# StepperDriver.net
KiCad netlist of a schematic drawn in EAGLE
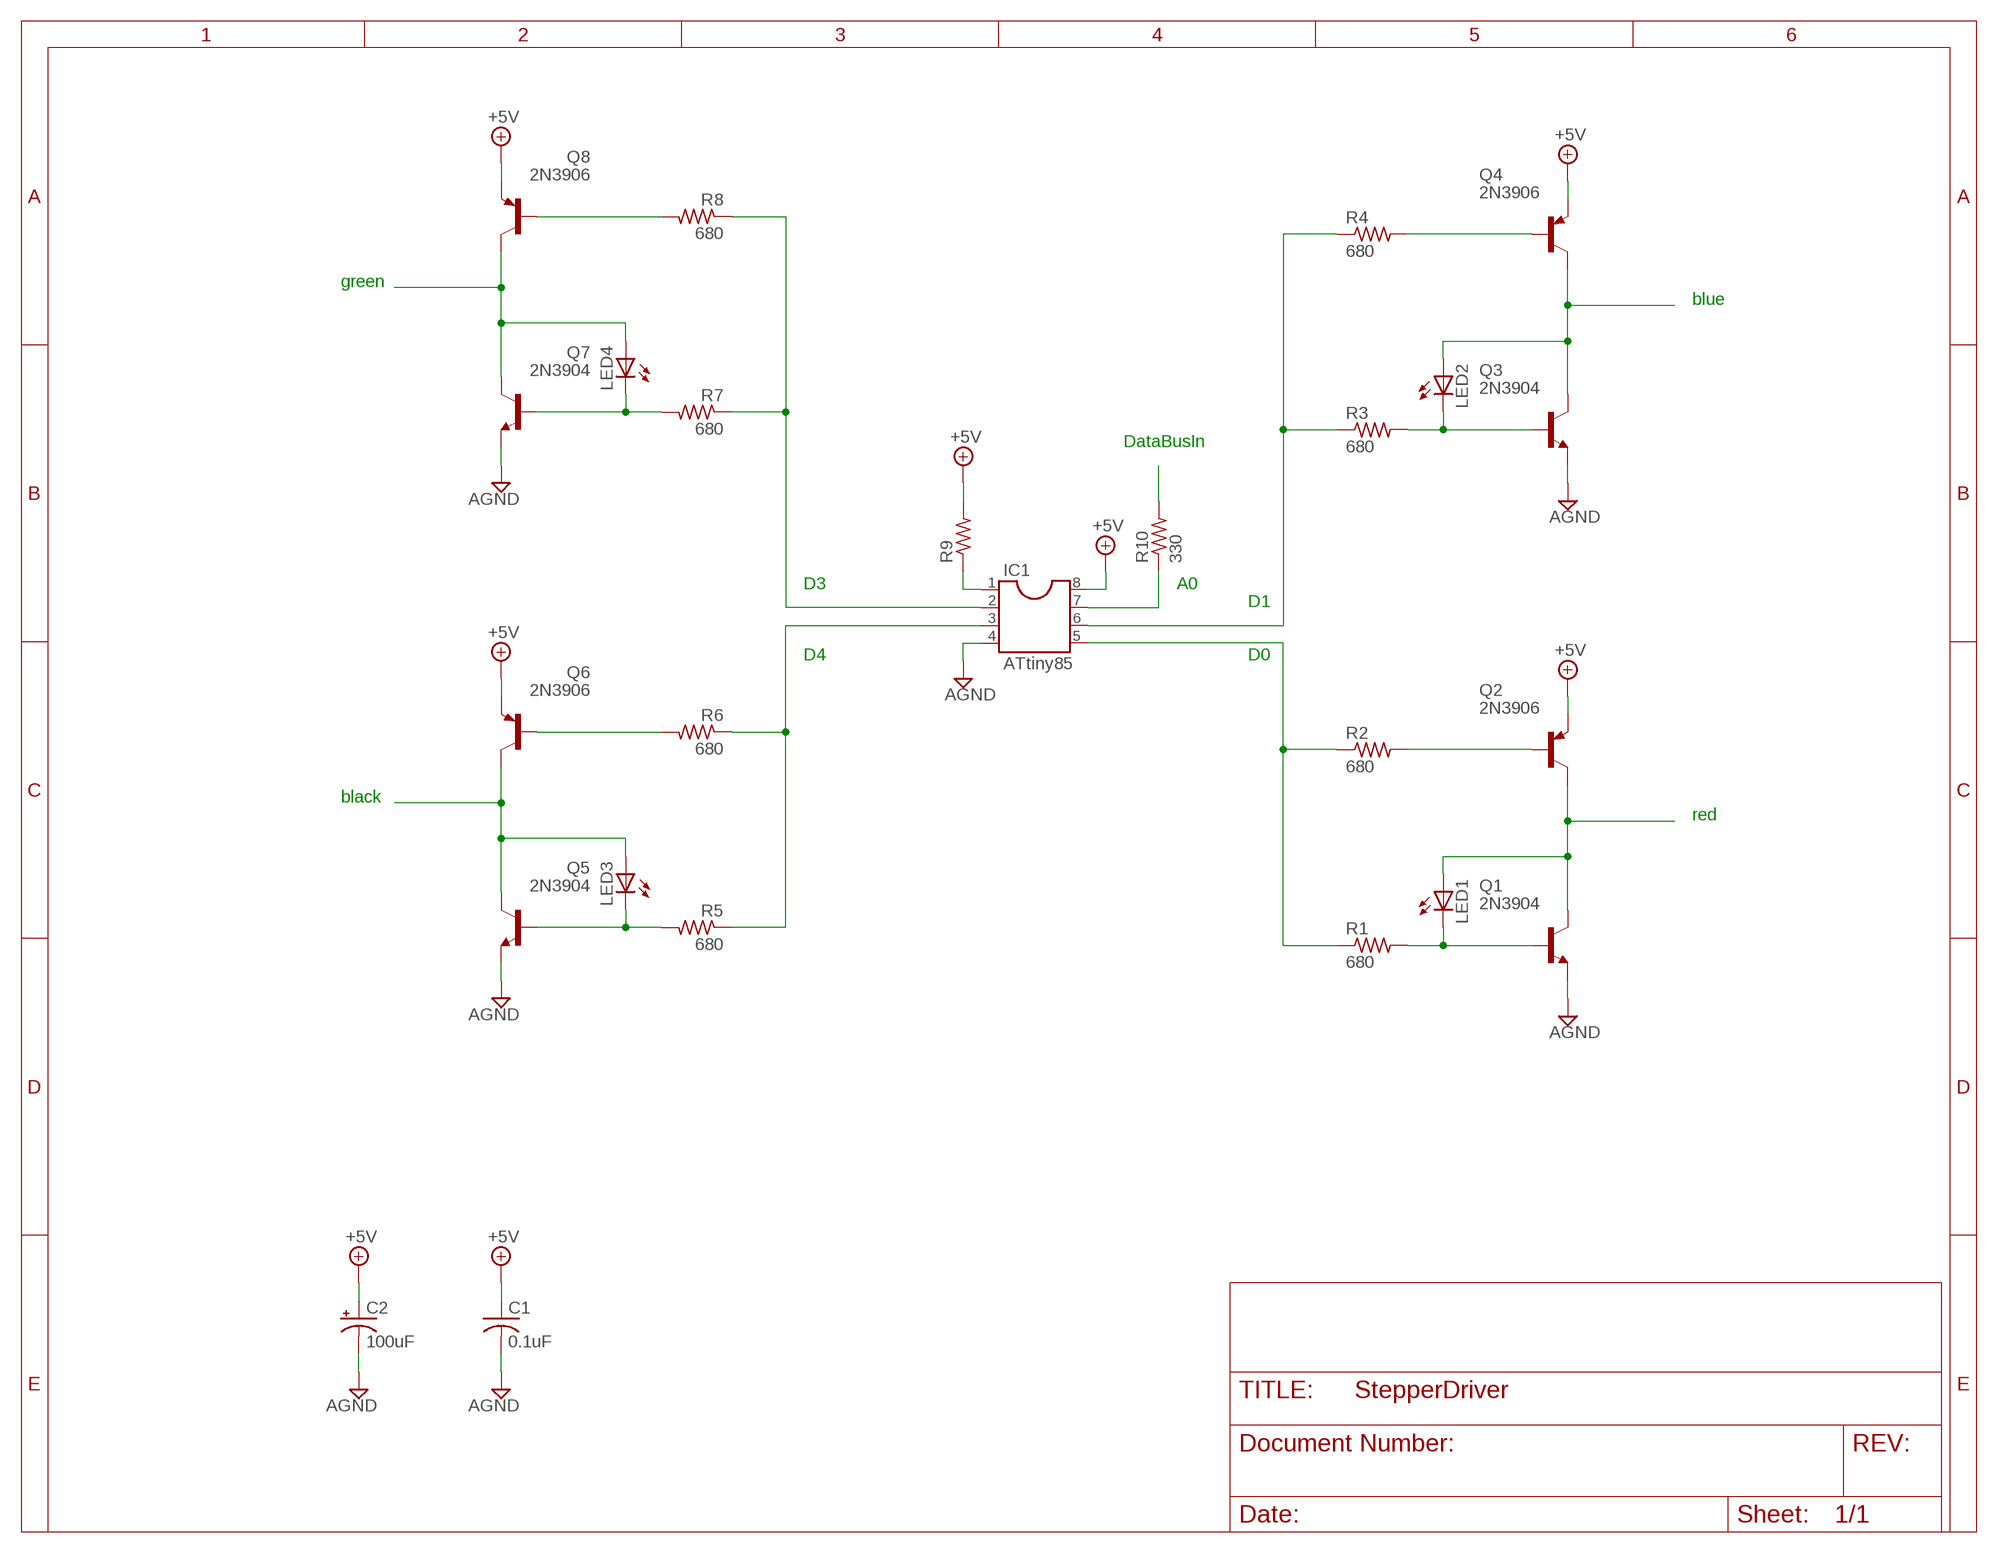
[diagram p0: schematic, sheet 1]

(export (version "E")
  (design (tool "Eeschema 10.0.6"))
  (components
    (comp (ref "C1")
      (value "0.1uF")
      (footprint "eagle-import:C025-050X050")
      (libsource (lib "eagle-import") (part "C-US025-050X050"))
    )
    (comp (ref "C2")
      (value "100uF")
      (footprint "eagle-import:E2,5-6E")
      (libsource (lib "eagle-import") (part "CPOL-USE2,5-6E"))
    )
    (comp (ref "IC1")
      (value "ATtiny85")
      (footprint "eagle-import:DIL08")
      (libsource (lib "eagle-import") (part "DIL8"))
    )
    (comp (ref "LED1")
      (value "LED5MM")
      (footprint "eagle-import:LED5MM")
      (libsource (lib "eagle-import") (part "LED5MM"))
    )
    (comp (ref "LED2")
      (value "LED5MM")
      (footprint "eagle-import:LED5MM")
      (libsource (lib "eagle-import") (part "LED5MM"))
    )
    (comp (ref "LED3")
      (value "LED5MM")
      (footprint "eagle-import:LED5MM")
      (libsource (lib "eagle-import") (part "LED5MM"))
    )
    (comp (ref "LED4")
      (value "LED5MM")
      (footprint "eagle-import:LED5MM")
      (libsource (lib "eagle-import") (part "LED5MM"))
    )
    (comp (ref "Q1")
      (value "2N3904")
      (footprint "eagle-import:TO92")
      (libsource (lib "eagle-import") (part "2N3904"))
    )
    (comp (ref "Q2")
      (value "2N3906")
      (footprint "eagle-import:TO92")
      (libsource (lib "eagle-import") (part "2N3906"))
    )
    (comp (ref "Q3")
      (value "2N3904")
      (footprint "eagle-import:TO92")
      (libsource (lib "eagle-import") (part "2N3904"))
    )
    (comp (ref "Q4")
      (value "2N3906")
      (footprint "eagle-import:TO92")
      (libsource (lib "eagle-import") (part "2N3906"))
    )
    (comp (ref "Q5")
      (value "2N3904")
      (footprint "eagle-import:TO92")
      (libsource (lib "eagle-import") (part "2N3904"))
    )
    (comp (ref "Q6")
      (value "2N3906")
      (footprint "eagle-import:TO92")
      (libsource (lib "eagle-import") (part "2N3906"))
    )
    (comp (ref "Q7")
      (value "2N3904")
      (footprint "eagle-import:TO92")
      (libsource (lib "eagle-import") (part "2N3904"))
    )
    (comp (ref "Q8")
      (value "2N3906")
      (footprint "eagle-import:TO92")
      (libsource (lib "eagle-import") (part "2N3906"))
    )
    (comp (ref "R1")
      (value "680")
      (footprint "eagle-import:VMTA55")
      (libsource (lib "eagle-import") (part "R-US_VMTA55"))
    )
    (comp (ref "R2")
      (value "680")
      (footprint "eagle-import:VMTA55")
      (libsource (lib "eagle-import") (part "R-US_VMTA55"))
    )
    (comp (ref "R3")
      (value "680")
      (footprint "eagle-import:VMTA55")
      (libsource (lib "eagle-import") (part "R-US_VMTA55"))
    )
    (comp (ref "R4")
      (value "680")
      (footprint "eagle-import:VMTA55")
      (libsource (lib "eagle-import") (part "R-US_VMTA55"))
    )
    (comp (ref "R5")
      (value "680")
      (footprint "eagle-import:VMTA55")
      (libsource (lib "eagle-import") (part "R-US_VMTA55"))
    )
    (comp (ref "R6")
      (value "680")
      (footprint "eagle-import:VMTA55")
      (libsource (lib "eagle-import") (part "R-US_VMTA55"))
    )
    (comp (ref "R7")
      (value "680")
      (footprint "eagle-import:VMTA55")
      (libsource (lib "eagle-import") (part "R-US_VMTA55"))
    )
    (comp (ref "R8")
      (value "680")
      (footprint "eagle-import:VMTA55")
      (libsource (lib "eagle-import") (part "R-US_VMTA55"))
    )
    (comp (ref "R9")
      (value "R-US_VMTA55")
      (footprint "eagle-import:VMTA55")
      (libsource (lib "eagle-import") (part "R-US_VMTA55"))
    )
    (comp (ref "R10")
      (value "330")
      (footprint "eagle-import:VMTA55")
      (libsource (lib "eagle-import") (part "R-US_VMTA55"))
    )
  )
  (nets
    (net (code "1") (name "+5V") (class "Default")
      (node (ref "C1") (pin "1") (pinfunction "1_1") (pintype "passive"))
      (node (ref "C2") (pin "+") (pinfunction "+_+") (pintype "passive"))
      (node (ref "IC1") (pin "8") (pinfunction "8_8") (pintype "passive"))
      (node (ref "Q2") (pin "3") (pinfunction "E_3") (pintype "passive"))
      (node (ref "Q4") (pin "3") (pinfunction "E_3") (pintype "passive"))
      (node (ref "Q6") (pin "3") (pinfunction "E_3") (pintype "passive"))
      (node (ref "Q8") (pin "3") (pinfunction "E_3") (pintype "passive"))
      (node (ref "R9") (pin "2") (pinfunction "2_2") (pintype "passive"))
    )
    (net (code "2") (name "AGND") (class "Default")
      (node (ref "C1") (pin "2") (pinfunction "2_2") (pintype "passive"))
      (node (ref "C2") (pin "-") (pinfunction "-_-") (pintype "passive"))
      (node (ref "IC1") (pin "4") (pinfunction "4_4") (pintype "passive"))
      (node (ref "Q1") (pin "3") (pinfunction "E_3") (pintype "passive"))
      (node (ref "Q3") (pin "3") (pinfunction "E_3") (pintype "passive"))
      (node (ref "Q5") (pin "3") (pinfunction "E_3") (pintype "passive"))
      (node (ref "Q7") (pin "3") (pinfunction "E_3") (pintype "passive"))
    )
    (net (code "3") (name "Net-(IC1-Pad1)") (class "Default")
      (node (ref "IC1") (pin "1") (pinfunction "1_1") (pintype "passive"))
      (node (ref "R9") (pin "1") (pinfunction "1_1") (pintype "passive"))
    )
    (net (code "4") (name "Net-(IC1-Pad2)") (class "Default")
      (node (ref "IC1") (pin "2") (pinfunction "2_2") (pintype "passive"))
      (node (ref "R7") (pin "1") (pinfunction "1_1") (pintype "passive"))
      (node (ref "R8") (pin "1") (pinfunction "1_1") (pintype "passive"))
    )
    (net (code "5") (name "Net-(IC1-Pad3)") (class "Default")
      (node (ref "IC1") (pin "3") (pinfunction "3_3") (pintype "passive"))
      (node (ref "R5") (pin "1") (pinfunction "1_1") (pintype "passive"))
      (node (ref "R6") (pin "1") (pinfunction "1_1") (pintype "passive"))
    )
    (net (code "6") (name "Net-(IC1-Pad5)") (class "Default")
      (node (ref "IC1") (pin "5") (pinfunction "5_5") (pintype "passive"))
      (node (ref "R1") (pin "1") (pinfunction "1_1") (pintype "passive"))
      (node (ref "R2") (pin "1") (pinfunction "1_1") (pintype "passive"))
    )
    (net (code "7") (name "Net-(IC1-Pad6)") (class "Default")
      (node (ref "IC1") (pin "6") (pinfunction "6_6") (pintype "passive"))
      (node (ref "R3") (pin "1") (pinfunction "1_1") (pintype "passive"))
      (node (ref "R4") (pin "1") (pinfunction "1_1") (pintype "passive"))
    )
    (net (code "8") (name "Net-(IC1-Pad7)") (class "Default")
      (node (ref "IC1") (pin "7") (pinfunction "7_7") (pintype "passive"))
      (node (ref "R10") (pin "1") (pinfunction "1_1") (pintype "passive"))
    )
    (net (code "9") (name "Net-(LED1-C)") (class "Default")
      (node (ref "LED1") (pin "K") (pinfunction "C_K") (pintype "passive"))
      (node (ref "Q1") (pin "2") (pinfunction "B_2") (pintype "passive"))
      (node (ref "R1") (pin "2") (pinfunction "2_2") (pintype "passive"))
    )
    (net (code "10") (name "Net-(LED2-C)") (class "Default")
      (node (ref "LED2") (pin "K") (pinfunction "C_K") (pintype "passive"))
      (node (ref "Q3") (pin "2") (pinfunction "B_2") (pintype "passive"))
      (node (ref "R3") (pin "2") (pinfunction "2_2") (pintype "passive"))
    )
    (net (code "11") (name "Net-(LED3-C)") (class "Default")
      (node (ref "LED3") (pin "K") (pinfunction "C_K") (pintype "passive"))
      (node (ref "Q5") (pin "2") (pinfunction "B_2") (pintype "passive"))
      (node (ref "R5") (pin "2") (pinfunction "2_2") (pintype "passive"))
    )
    (net (code "12") (name "Net-(LED4-C)") (class "Default")
      (node (ref "LED4") (pin "K") (pinfunction "C_K") (pintype "passive"))
      (node (ref "Q7") (pin "2") (pinfunction "B_2") (pintype "passive"))
      (node (ref "R7") (pin "2") (pinfunction "2_2") (pintype "passive"))
    )
    (net (code "13") (name "Net-(Q1-C)") (class "Default")
      (node (ref "LED1") (pin "A") (pinfunction "A_A") (pintype "passive"))
      (node (ref "Q1") (pin "1") (pinfunction "C_1") (pintype "passive"))
      (node (ref "Q2") (pin "1") (pinfunction "C_1") (pintype "passive"))
    )
    (net (code "14") (name "Net-(Q2-B)") (class "Default")
      (node (ref "Q2") (pin "2") (pinfunction "B_2") (pintype "passive"))
      (node (ref "R2") (pin "2") (pinfunction "2_2") (pintype "passive"))
    )
    (net (code "15") (name "Net-(Q3-C)") (class "Default")
      (node (ref "LED2") (pin "A") (pinfunction "A_A") (pintype "passive"))
      (node (ref "Q3") (pin "1") (pinfunction "C_1") (pintype "passive"))
      (node (ref "Q4") (pin "1") (pinfunction "C_1") (pintype "passive"))
    )
    (net (code "16") (name "Net-(Q4-B)") (class "Default")
      (node (ref "Q4") (pin "2") (pinfunction "B_2") (pintype "passive"))
      (node (ref "R4") (pin "2") (pinfunction "2_2") (pintype "passive"))
    )
    (net (code "17") (name "Net-(Q5-C)") (class "Default")
      (node (ref "LED3") (pin "A") (pinfunction "A_A") (pintype "passive"))
      (node (ref "Q5") (pin "1") (pinfunction "C_1") (pintype "passive"))
      (node (ref "Q6") (pin "1") (pinfunction "C_1") (pintype "passive"))
    )
    (net (code "18") (name "Net-(Q6-B)") (class "Default")
      (node (ref "Q6") (pin "2") (pinfunction "B_2") (pintype "passive"))
      (node (ref "R6") (pin "2") (pinfunction "2_2") (pintype "passive"))
    )
    (net (code "19") (name "Net-(Q7-C)") (class "Default")
      (node (ref "LED4") (pin "A") (pinfunction "A_A") (pintype "passive"))
      (node (ref "Q7") (pin "1") (pinfunction "C_1") (pintype "passive"))
      (node (ref "Q8") (pin "1") (pinfunction "C_1") (pintype "passive"))
    )
    (net (code "20") (name "Net-(Q8-B)") (class "Default")
      (node (ref "Q8") (pin "2") (pinfunction "B_2") (pintype "passive"))
      (node (ref "R8") (pin "2") (pinfunction "2_2") (pintype "passive"))
    )
    (net (code "21") (name "unconnected-(R10-Pad2)") (class "Default")
      (node (ref "R10") (pin "2") (pinfunction "2_2") (pintype "passive"))
    )
  )
)
